# Makesafe_OptocoupledZCD.net
KiCad netlist of a schematic drawn in EAGLE
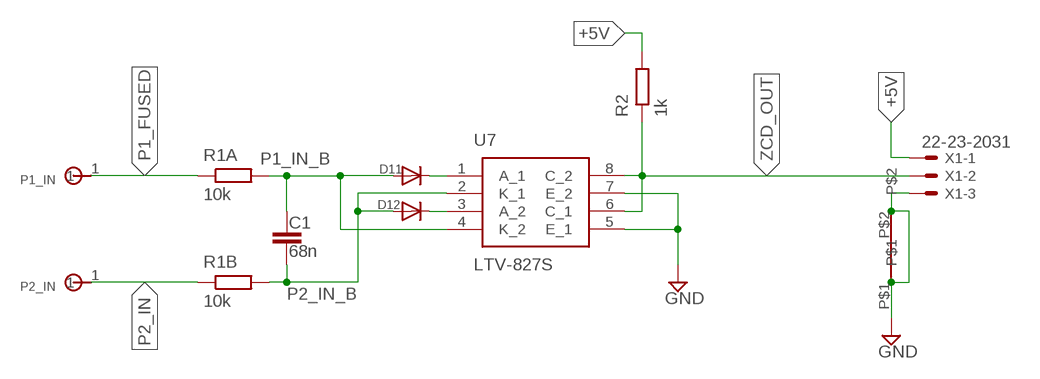
[diagram p0: schematic, sheet 1]

(export (version "E")
  (design (tool "Eeschema 10.0.6"))
  (components
    (comp (ref "C1")
      (value "68n")
      (footprint "eagle-import:0204_7_TH")
      (libsource (lib "eagle-import") (part "TH_CAPACITOR"))
    )
    (comp (ref "D11")
      (value "DIODE")
      (footprint "eagle-import:0204_7_TH")
      (libsource (lib "eagle-import") (part "DIODE"))
    )
    (comp (ref "D12")
      (value "DIODE")
      (footprint "eagle-import:0204_7_TH")
      (libsource (lib "eagle-import") (part "DIODE"))
    )
    (comp (ref "P1_IN")
      (value "90MIL_TERMINAL")
      (footprint "eagle-import:90MIL_TERMINAL")
      (libsource (lib "eagle-import") (part "90MIL_TERMINAL"))
    )
    (comp (ref "P2_IN")
      (value "90MIL_TERMINAL")
      (footprint "eagle-import:90MIL_TERMINAL")
      (libsource (lib "eagle-import") (part "90MIL_TERMINAL"))
    )
    (comp (ref "R1A")
      (value "10k")
      (footprint "eagle-import:0204_7_TH")
      (libsource (lib "eagle-import") (part "TH_RESISTOR"))
    )
    (comp (ref "R1B")
      (value "10k")
      (footprint "eagle-import:0204_7_TH")
      (libsource (lib "eagle-import") (part "TH_RESISTOR"))
    )
    (comp (ref "R2")
      (value "1k")
      (footprint "eagle-import:0204_7_TH")
      (libsource (lib "eagle-import") (part "TH_RESISTOR"))
    )
    (comp (ref "U$1")
      (value "JUMPER")
      (footprint "eagle-import:0204_7_TH")
      (libsource (lib "eagle-import") (part "JUMPER"))
    )
    (comp (ref "U7")
      (value "LTV-827S")
      (footprint "eagle-import:SOP254P1016X460-8N")
      (fields (field (name "MOUSER_PART_NUMBER") "859-LTV-827S"))
      (libsource (lib "eagle-import") (part "LTV-827S"))
    )
    (comp (ref "X1")
      (value "22-23-2031")
      (footprint "eagle-import:22-23-2031")
      (fields (field (name "MF") "MOLEX"))
      (libsource (lib "eagle-import") (part "22-23-2031"))
    )
  )
  (nets
    (net (code "1") (name "+5V") (class "Default")
      (node (ref "R2") (pin "P$2") (pinfunction "P$2_P$2") (pintype "bidirectional"))
      (node (ref "X1") (pin "1") (pinfunction "S_1") (pintype "passive"))
    )
    (net (code "2") (name "/P1_IN_B") (class "Default")
      (node (ref "C1") (pin "P$1") (pinfunction "1_P$1") (pintype "passive"))
      (node (ref "D11") (pin "P$1") (pinfunction "A_P$1") (pintype "passive"))
      (node (ref "R1A") (pin "P$2") (pinfunction "P$2_P$2") (pintype "bidirectional"))
      (node (ref "U7") (pin "4") (pinfunction "K_2_4") (pintype "bidirectional"))
    )
    (net (code "3") (name "/P2_IN_B") (class "Default")
      (node (ref "C1") (pin "P$2") (pinfunction "2_P$2") (pintype "passive"))
      (node (ref "D12") (pin "P$1") (pinfunction "A_P$1") (pintype "passive"))
      (node (ref "R1B") (pin "P$2") (pinfunction "P$2_P$2") (pintype "bidirectional"))
      (node (ref "U7") (pin "2") (pinfunction "K_1_2") (pintype "bidirectional"))
    )
    (net (code "4") (name "GND") (class "Default")
      (node (ref "U$1") (pin "P$1") (pinfunction "P$1_P$1") (pintype "bidirectional"))
      (node (ref "U$1") (pin "P$2") (pinfunction "P$2_P$2") (pintype "bidirectional"))
      (node (ref "U7") (pin "5") (pinfunction "E_1_5") (pintype "bidirectional"))
      (node (ref "U7") (pin "7") (pinfunction "E_2_7") (pintype "bidirectional"))
      (node (ref "X1") (pin "3") (pinfunction "S_3") (pintype "passive"))
    )
    (net (code "5") (name "Net-(D11-C)") (class "Default")
      (node (ref "D11") (pin "P$2") (pinfunction "C_P$2") (pintype "passive"))
      (node (ref "U7") (pin "1") (pinfunction "A_1_1") (pintype "bidirectional"))
    )
    (net (code "6") (name "Net-(D12-C)") (class "Default")
      (node (ref "D12") (pin "P$2") (pinfunction "C_P$2") (pintype "passive"))
      (node (ref "U7") (pin "3") (pinfunction "A_2_3") (pintype "bidirectional"))
    )
    (net (code "7") (name "P1_FUSED") (class "Default")
      (node (ref "P1_IN") (pin "1") (pinfunction "1_1") (pintype "passive"))
      (node (ref "R1A") (pin "P$1") (pinfunction "P$1_P$1") (pintype "bidirectional"))
    )
    (net (code "8") (name "P2_IN") (class "Default")
      (node (ref "P2_IN") (pin "1") (pinfunction "1_1") (pintype "passive"))
      (node (ref "R1B") (pin "P$1") (pinfunction "P$1_P$1") (pintype "bidirectional"))
    )
    (net (code "9") (name "ZCD_OUT") (class "Default")
      (node (ref "R2") (pin "P$1") (pinfunction "P$1_P$1") (pintype "bidirectional"))
      (node (ref "U7") (pin "6") (pinfunction "C_1_6") (pintype "bidirectional"))
      (node (ref "U7") (pin "8") (pinfunction "C_2_8") (pintype "bidirectional"))
      (node (ref "X1") (pin "2") (pinfunction "S_2") (pintype "passive"))
    )
  )
)
